# codec.net
KiCad netlist of a schematic drawn in Altium Designer
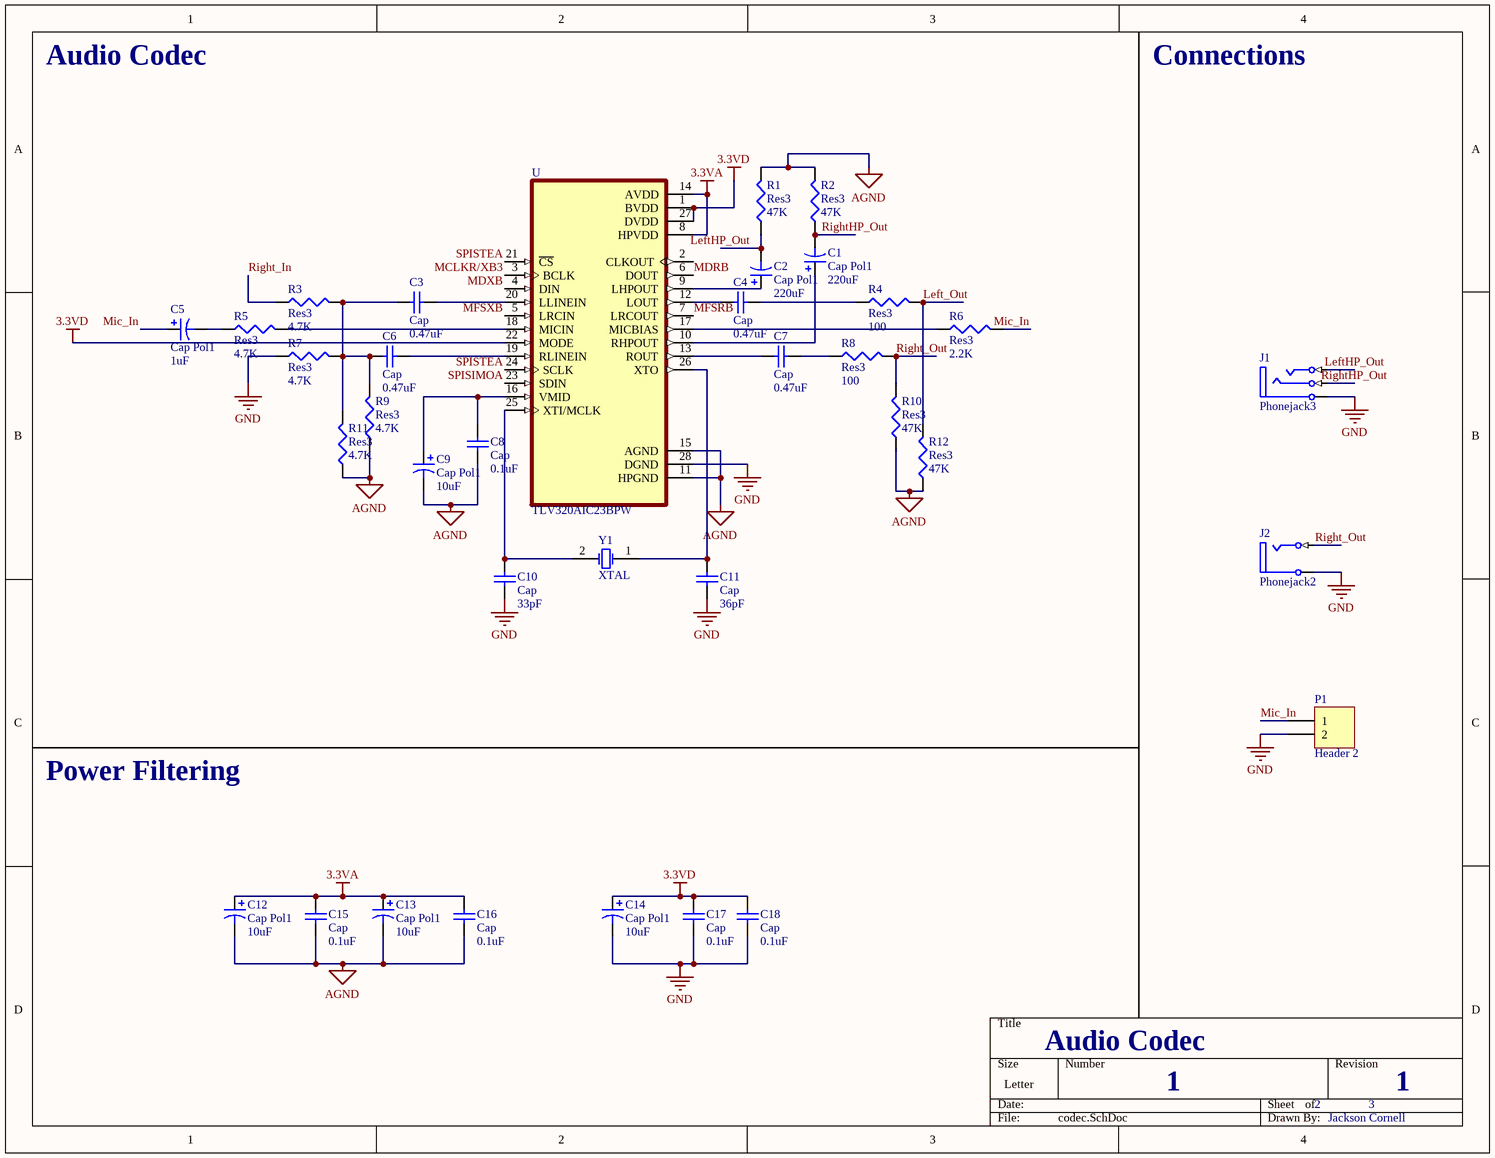
[diagram p0: codec.SchDoc]

(export (version "E")
  (design (tool "Eeschema 10.0.6"))
  (components
    (comp (ref "C1")
      (value "Cap Pol1")
      (footprint "RB7.6-15")
      (description "Polarized Capacitor (Radial)")
      (fields (field (name "ALTIUM_VALUE") "220uF") (field (name "PUBLISHER") "Altium Limited"))
      (libsource (lib "Miscellaneous Devices") (part "Cap Pol1"))
    )
    (comp (ref "C2")
      (value "Cap Pol1")
      (footprint "RB7.6-15")
      (description "Polarized Capacitor (Radial)")
      (fields (field (name "ALTIUM_VALUE") "220uF") (field (name "PUBLISHER") "Altium Limited"))
      (libsource (lib "Miscellaneous Devices") (part "Cap Pol1"))
    )
    (comp (ref "C3")
      (value "Cap")
      (footprint "RAD-0.3")
      (description "Capacitor")
      (fields (field (name "ALTIUM_VALUE") "0.47uF") (field (name "PUBLISHER") "Altium Limited"))
      (libsource (lib "Miscellaneous Devices") (part "Cap"))
    )
    (comp (ref "C4")
      (value "Cap")
      (footprint "RAD-0.3")
      (description "Capacitor")
      (fields (field (name "ALTIUM_VALUE") "0.47uF") (field (name "PUBLISHER") "Altium Limited"))
      (libsource (lib "Miscellaneous Devices") (part "Cap"))
    )
    (comp (ref "C5")
      (value "Cap Pol1")
      (footprint "RB7.6-15")
      (description "Polarized Capacitor (Radial)")
      (fields (field (name "ALTIUM_VALUE") "1uF") (field (name "PUBLISHER") "Altium Limited"))
      (libsource (lib "Miscellaneous Devices") (part "Cap Pol1"))
    )
    (comp (ref "C6")
      (value "Cap")
      (footprint "RAD-0.3")
      (description "Capacitor")
      (fields (field (name "ALTIUM_VALUE") "0.47uF") (field (name "PUBLISHER") "Altium Limited"))
      (libsource (lib "Miscellaneous Devices") (part "Cap"))
    )
    (comp (ref "C7")
      (value "Cap")
      (footprint "RAD-0.3")
      (description "Capacitor")
      (fields (field (name "ALTIUM_VALUE") "0.47uF") (field (name "PUBLISHER") "Altium Limited"))
      (libsource (lib "Miscellaneous Devices") (part "Cap"))
    )
    (comp (ref "C8")
      (value "Cap")
      (footprint "RAD-0.3")
      (description "Capacitor")
      (fields (field (name "ALTIUM_VALUE") "0.1uF") (field (name "PUBLISHER") "Altium Limited"))
      (libsource (lib "Miscellaneous Devices") (part "Cap"))
    )
    (comp (ref "C9")
      (value "Cap Pol1")
      (footprint "RB7.6-15")
      (description "Polarized Capacitor (Radial)")
      (fields (field (name "ALTIUM_VALUE") "10uF") (field (name "PUBLISHER") "Altium Limited"))
      (libsource (lib "Miscellaneous Devices") (part "Cap Pol1"))
    )
    (comp (ref "C10")
      (value "Cap")
      (footprint "RAD-0.3")
      (description "Capacitor")
      (fields (field (name "ALTIUM_VALUE") "33pF") (field (name "PUBLISHER") "Altium Limited"))
      (libsource (lib "Miscellaneous Devices") (part "Cap"))
    )
    (comp (ref "C11")
      (value "Cap")
      (footprint "RAD-0.3")
      (description "Capacitor")
      (fields (field (name "ALTIUM_VALUE") "36pF") (field (name "PUBLISHER") "Altium Limited"))
      (libsource (lib "Miscellaneous Devices") (part "Cap"))
    )
    (comp (ref "C12")
      (value "Cap Pol1")
      (footprint "RB7.6-15")
      (description "Polarized Capacitor (Radial)")
      (fields (field (name "ALTIUM_VALUE") "10uF") (field (name "PUBLISHER") "Altium Limited"))
      (libsource (lib "Miscellaneous Devices") (part "Cap Pol1"))
    )
    (comp (ref "C13")
      (value "Cap Pol1")
      (footprint "RB7.6-15")
      (description "Polarized Capacitor (Radial)")
      (fields (field (name "ALTIUM_VALUE") "10uF") (field (name "PUBLISHER") "Altium Limited"))
      (libsource (lib "Miscellaneous Devices") (part "Cap Pol1"))
    )
    (comp (ref "C14")
      (value "Cap Pol1")
      (footprint "RB7.6-15")
      (description "Polarized Capacitor (Radial)")
      (fields (field (name "ALTIUM_VALUE") "10uF") (field (name "PUBLISHER") "Altium Limited"))
      (libsource (lib "Miscellaneous Devices") (part "Cap Pol1"))
    )
    (comp (ref "C15")
      (value "Cap")
      (footprint "RAD-0.3")
      (description "Capacitor")
      (fields (field (name "ALTIUM_VALUE") "0.1uF") (field (name "PUBLISHER") "Altium Limited"))
      (libsource (lib "Miscellaneous Devices") (part "Cap"))
    )
    (comp (ref "C16")
      (value "Cap")
      (footprint "RAD-0.3")
      (description "Capacitor")
      (fields (field (name "ALTIUM_VALUE") "0.1uF") (field (name "PUBLISHER") "Altium Limited"))
      (libsource (lib "Miscellaneous Devices") (part "Cap"))
    )
    (comp (ref "C17")
      (value "Cap")
      (footprint "RAD-0.3")
      (description "Capacitor")
      (fields (field (name "ALTIUM_VALUE") "0.1uF") (field (name "PUBLISHER") "Altium Limited"))
      (libsource (lib "Miscellaneous Devices") (part "Cap"))
    )
    (comp (ref "C18")
      (value "Cap")
      (footprint "RAD-0.3")
      (description "Capacitor")
      (fields (field (name "ALTIUM_VALUE") "0.1uF") (field (name "PUBLISHER") "Altium Limited"))
      (libsource (lib "Miscellaneous Devices") (part "Cap"))
    )
    (comp (ref "J1")
      (value "Phonejack3")
      (footprint "JACK/6-V3")
      (description "Jack Socket, 1/4\" [6.5mm], Thru-Hole, Vertical, 3-Conductor Open Circuit (Non-Normalling)")
      (fields (field (name "PUBLISHER") "Altium Limited"))
      (libsource (lib "Miscellaneous Connectors") (part "Phonejack3"))
    )
    (comp (ref "J2")
      (value "Phonejack2")
      (footprint "JACK/6-V2")
      (description "Jack Socket, 1/4\" [6.5mm], Thru-Hole, Vertical, 2-Conductor Open Circuit")
      (fields (field (name "PUBLISHER") "Altium Limited"))
      (libsource (lib "Miscellaneous Connectors") (part "Phonejack2"))
    )
    (comp (ref "P1")
      (value "Header 2")
      (footprint "HDR1X2")
      (description "Header, 2-Pin")
      (fields (field (name "PUBLISHER") "Altium Limited"))
      (libsource (lib "Miscellaneous Connectors") (part "Header 2"))
    )
    (comp (ref "R1")
      (value "Res3")
      (footprint "J1-0603")
      (description "Resistor")
      (fields (field (name "ALTIUM_VALUE") "47K") (field (name "PUBLISHER") "Altium Limited"))
      (libsource (lib "Miscellaneous Devices") (part "Res3"))
    )
    (comp (ref "R2")
      (value "Res3")
      (footprint "J1-0603")
      (description "Resistor")
      (fields (field (name "ALTIUM_VALUE") "47K") (field (name "PUBLISHER") "Altium Limited"))
      (libsource (lib "Miscellaneous Devices") (part "Res3"))
    )
    (comp (ref "R3")
      (value "Res3")
      (footprint "J1-0603")
      (description "Resistor")
      (fields (field (name "ALTIUM_VALUE") "4.7K") (field (name "PUBLISHER") "Altium Limited"))
      (libsource (lib "Miscellaneous Devices") (part "Res3"))
    )
    (comp (ref "R4")
      (value "Res3")
      (footprint "J1-0603")
      (description "Resistor")
      (fields (field (name "ALTIUM_VALUE") "100") (field (name "PUBLISHER") "Altium Limited"))
      (libsource (lib "Miscellaneous Devices") (part "Res3"))
    )
    (comp (ref "R5")
      (value "Res3")
      (footprint "J1-0603")
      (description "Resistor")
      (fields (field (name "ALTIUM_VALUE") "4.7K") (field (name "PUBLISHER") "Altium Limited"))
      (libsource (lib "Miscellaneous Devices") (part "Res3"))
    )
    (comp (ref "R6")
      (value "Res3")
      (footprint "J1-0603")
      (description "Resistor")
      (fields (field (name "ALTIUM_VALUE") "2.2K") (field (name "PUBLISHER") "Altium Limited"))
      (libsource (lib "Miscellaneous Devices") (part "Res3"))
    )
    (comp (ref "R7")
      (value "Res3")
      (footprint "J1-0603")
      (description "Resistor")
      (fields (field (name "ALTIUM_VALUE") "4.7K") (field (name "PUBLISHER") "Altium Limited"))
      (libsource (lib "Miscellaneous Devices") (part "Res3"))
    )
    (comp (ref "R8")
      (value "Res3")
      (footprint "J1-0603")
      (description "Resistor")
      (fields (field (name "ALTIUM_VALUE") "100") (field (name "PUBLISHER") "Altium Limited"))
      (libsource (lib "Miscellaneous Devices") (part "Res3"))
    )
    (comp (ref "R9")
      (value "Res3")
      (footprint "J1-0603")
      (description "Resistor")
      (fields (field (name "ALTIUM_VALUE") "4.7K") (field (name "PUBLISHER") "Altium Limited"))
      (libsource (lib "Miscellaneous Devices") (part "Res3"))
    )
    (comp (ref "R10")
      (value "Res3")
      (footprint "J1-0603")
      (description "Resistor")
      (fields (field (name "ALTIUM_VALUE") "47K") (field (name "PUBLISHER") "Altium Limited"))
      (libsource (lib "Miscellaneous Devices") (part "Res3"))
    )
    (comp (ref "R11")
      (value "Res3")
      (footprint "J1-0603")
      (description "Resistor")
      (fields (field (name "ALTIUM_VALUE") "4.7K") (field (name "PUBLISHER") "Altium Limited"))
      (libsource (lib "Miscellaneous Devices") (part "Res3"))
    )
    (comp (ref "R12")
      (value "Res3")
      (footprint "J1-0603")
      (description "Resistor")
      (fields (field (name "ALTIUM_VALUE") "47K") (field (name "PUBLISHER") "Altium Limited"))
      (libsource (lib "Miscellaneous Devices") (part "Res3"))
    )
    (comp (ref "U")
      (value "TLV320AIC23BPW")
      (footprint "SOP65P640X120-28N")
      (description "Low-Power Stereo CODEC with HP Amplifier 28-TSSOP -10 to 70")
      (fields (field (name "MF") "Texas Instruments"))
      (libsource (lib "TLV320AIC23BPW") (part "TLV320AIC23BPW"))
    )
    (comp (ref "Y1")
      (value "XTAL")
      (footprint "R38")
      (description "Crystal Oscillator")
      (fields (field (name "PUBLISHER") "Altium Limited"))
      (libsource (lib "Miscellaneous Devices") (part "XTAL"))
    )
  )
  (nets
    (net (code "1") (name "/LeftHP_Out") (class "Default")
      (node (ref "C2") (pin "2") (pinfunction "2_2") (pintype "passive"))
      (node (ref "J1") (pin "1") (pinfunction "T_1") (pintype "input"))
      (node (ref "R1") (pin "1") (pinfunction "1_1") (pintype "passive"))
    )
    (net (code "2") (name "/Left_Out") (class "Default")
      (node (ref "R12") (pin "2") (pinfunction "2_2") (pintype "passive"))
      (node (ref "R4") (pin "2") (pinfunction "2_2") (pintype "passive"))
    )
    (net (code "3") (name "/MCLKR{slash}XB3") (class "Default")
      (node (ref "U") (pin "3") (pinfunction "BCLK_3") (pintype "input"))
    )
    (net (code "4") (name "/MDRB") (class "Default")
      (node (ref "U") (pin "6") (pinfunction "DOUT_6") (pintype "output"))
    )
    (net (code "5") (name "/MDXB") (class "Default")
      (node (ref "U") (pin "4") (pinfunction "DIN_4") (pintype "input"))
    )
    (net (code "6") (name "/MFSRB") (class "Default")
      (node (ref "U") (pin "7") (pinfunction "LRCOUT_7") (pintype "output"))
    )
    (net (code "7") (name "/MFSXB") (class "Default")
      (node (ref "U") (pin "5") (pinfunction "LRCIN_5") (pintype "input"))
    )
    (net (code "8") (name "/Mic_In") (class "Default")
      (node (ref "C5") (pin "1") (pinfunction "1_1") (pintype "passive"))
      (node (ref "P1") (pin "1") (pinfunction "1_1") (pintype "passive"))
      (node (ref "R6") (pin "2") (pinfunction "2_2") (pintype "passive"))
    )
    (net (code "9") (name "/RightHP_Out") (class "Default")
      (node (ref "C1") (pin "2") (pinfunction "2_2") (pintype "passive"))
      (node (ref "J1") (pin "3") (pinfunction "R_3") (pintype "input"))
      (node (ref "R2") (pin "1") (pinfunction "1_1") (pintype "passive"))
    )
    (net (code "10") (name "/Right_In") (class "Default")
      (node (ref "R3") (pin "1") (pinfunction "1_1") (pintype "passive"))
    )
    (net (code "11") (name "/Right_Out") (class "Default")
      (node (ref "J2") (pin "1") (pinfunction "T_1") (pintype "input"))
      (node (ref "R10") (pin "2") (pinfunction "2_2") (pintype "passive"))
      (node (ref "R8") (pin "2") (pinfunction "2_2") (pintype "passive"))
    )
    (net (code "12") (name "/SPISIMOA") (class "Default")
      (node (ref "U") (pin "23") (pinfunction "SDIN_23") (pintype "input"))
    )
    (net (code "13") (name "/SPISTEA") (class "Default")
      (node (ref "U") (pin "21") (pinfunction "~{CS}_21") (pintype "input"))
      (node (ref "U") (pin "24") (pinfunction "SCLK_24") (pintype "input"))
    )
    (net (code "14") (name "3.3VA") (class "Default")
      (node (ref "C12") (pin "1") (pinfunction "1_1") (pintype "passive"))
      (node (ref "C13") (pin "1") (pinfunction "1_1") (pintype "passive"))
      (node (ref "C15") (pin "1") (pinfunction "1_1") (pintype "passive"))
      (node (ref "C16") (pin "1") (pinfunction "1_1") (pintype "passive"))
      (node (ref "U") (pin "14") (pinfunction "AVDD_14") (pintype "power_in"))
      (node (ref "U") (pin "8") (pinfunction "HPVDD_8") (pintype "power_in"))
    )
    (net (code "15") (name "3.3VD") (class "Default")
      (node (ref "C14") (pin "1") (pinfunction "1_1") (pintype "passive"))
      (node (ref "C17") (pin "2") (pinfunction "2_2") (pintype "passive"))
      (node (ref "C18") (pin "2") (pinfunction "2_2") (pintype "passive"))
      (node (ref "U") (pin "1") (pinfunction "BVDD_1") (pintype "power_in"))
      (node (ref "U") (pin "22") (pinfunction "MODE_22") (pintype "input"))
      (node (ref "U") (pin "27") (pinfunction "DVDD_27") (pintype "power_in"))
    )
    (net (code "16") (name "AGND") (class "Default")
      (node (ref "C12") (pin "2") (pinfunction "2_2") (pintype "passive"))
      (node (ref "C13") (pin "2") (pinfunction "2_2") (pintype "passive"))
      (node (ref "C15") (pin "2") (pinfunction "2_2") (pintype "passive"))
      (node (ref "C16") (pin "2") (pinfunction "2_2") (pintype "passive"))
      (node (ref "C8") (pin "1") (pinfunction "1_1") (pintype "passive"))
      (node (ref "C9") (pin "2") (pinfunction "2_2") (pintype "passive"))
      (node (ref "R1") (pin "2") (pinfunction "2_2") (pintype "passive"))
      (node (ref "R10") (pin "1") (pinfunction "1_1") (pintype "passive"))
      (node (ref "R11") (pin "1") (pinfunction "1_1") (pintype "passive"))
      (node (ref "R12") (pin "1") (pinfunction "1_1") (pintype "passive"))
      (node (ref "R2") (pin "2") (pinfunction "2_2") (pintype "passive"))
      (node (ref "R9") (pin "1") (pinfunction "1_1") (pintype "passive"))
      (node (ref "U") (pin "11") (pinfunction "HPGND_11") (pintype "power_in"))
      (node (ref "U") (pin "15") (pinfunction "AGND_15") (pintype "power_in"))
    )
    (net (code "17") (name "GND") (class "Default")
      (node (ref "C10") (pin "2") (pinfunction "2_2") (pintype "passive"))
      (node (ref "C11") (pin "2") (pinfunction "2_2") (pintype "passive"))
      (node (ref "C14") (pin "2") (pinfunction "2_2") (pintype "passive"))
      (node (ref "C17") (pin "1") (pinfunction "1_1") (pintype "passive"))
      (node (ref "C18") (pin "1") (pinfunction "1_1") (pintype "passive"))
      (node (ref "J1") (pin "5") (pinfunction "S_5") (pintype "power_in"))
      (node (ref "J2") (pin "5") (pinfunction "S_5") (pintype "power_in"))
      (node (ref "P1") (pin "2") (pinfunction "2_2") (pintype "passive"))
      (node (ref "R7") (pin "1") (pinfunction "1_1") (pintype "passive"))
      (node (ref "U") (pin "28") (pinfunction "DGND_28") (pintype "power_in"))
    )
    (net (code "18") (name "Net-(C3-Pad1)") (class "Default")
      (node (ref "C3") (pin "1") (pinfunction "1_1") (pintype "passive"))
      (node (ref "C6") (pin "1") (pinfunction "1_1") (pintype "passive"))
      (node (ref "R11") (pin "2") (pinfunction "2_2") (pintype "passive"))
      (node (ref "R3") (pin "2") (pinfunction "2_2") (pintype "passive"))
      (node (ref "R7") (pin "2") (pinfunction "2_2") (pintype "passive"))
      (node (ref "R9") (pin "2") (pinfunction "2_2") (pintype "passive"))
    )
    (net (code "19") (name "Net-(C4-Pad2)") (class "Default")
      (node (ref "C4") (pin "2") (pinfunction "2_2") (pintype "passive"))
      (node (ref "R4") (pin "1") (pinfunction "1_1") (pintype "passive"))
    )
    (net (code "20") (name "Net-(C5-Pad2)") (class "Default")
      (node (ref "C5") (pin "2") (pinfunction "2_2") (pintype "passive"))
      (node (ref "R5") (pin "1") (pinfunction "1_1") (pintype "passive"))
    )
    (net (code "21") (name "Net-(C7-Pad2)") (class "Default")
      (node (ref "C7") (pin "2") (pinfunction "2_2") (pintype "passive"))
      (node (ref "R8") (pin "1") (pinfunction "1_1") (pintype "passive"))
    )
    (net (code "22") (name "Net-(U-LHPOUT)") (class "Default")
      (node (ref "C2") (pin "1") (pinfunction "1_1") (pintype "passive"))
      (node (ref "U") (pin "9") (pinfunction "LHPOUT_9") (pintype "output"))
    )
    (net (code "23") (name "Net-(U-LLINEIN)") (class "Default")
      (node (ref "C3") (pin "2") (pinfunction "2_2") (pintype "passive"))
      (node (ref "U") (pin "20") (pinfunction "LLINEIN_20") (pintype "input"))
    )
    (net (code "24") (name "Net-(U-LOUT)") (class "Default")
      (node (ref "C4") (pin "1") (pinfunction "1_1") (pintype "passive"))
      (node (ref "U") (pin "12") (pinfunction "LOUT_12") (pintype "output"))
    )
    (net (code "25") (name "Net-(U-MICBIAS)") (class "Default")
      (node (ref "R6") (pin "1") (pinfunction "1_1") (pintype "passive"))
      (node (ref "U") (pin "17") (pinfunction "MICBIAS_17") (pintype "output"))
    )
    (net (code "26") (name "Net-(U-MICIN)") (class "Default")
      (node (ref "R5") (pin "2") (pinfunction "2_2") (pintype "passive"))
      (node (ref "U") (pin "18") (pinfunction "MICIN_18") (pintype "input"))
    )
    (net (code "27") (name "Net-(U-RHPOUT)") (class "Default")
      (node (ref "C1") (pin "1") (pinfunction "1_1") (pintype "passive"))
      (node (ref "U") (pin "10") (pinfunction "RHPOUT_10") (pintype "output"))
    )
    (net (code "28") (name "Net-(U-RLINEIN)") (class "Default")
      (node (ref "C6") (pin "2") (pinfunction "2_2") (pintype "passive"))
      (node (ref "U") (pin "19") (pinfunction "RLINEIN_19") (pintype "input"))
    )
    (net (code "29") (name "Net-(U-ROUT)") (class "Default")
      (node (ref "C7") (pin "1") (pinfunction "1_1") (pintype "passive"))
      (node (ref "U") (pin "13") (pinfunction "ROUT_13") (pintype "output"))
    )
    (net (code "30") (name "Net-(U-VMID)") (class "Default")
      (node (ref "C8") (pin "2") (pinfunction "2_2") (pintype "passive"))
      (node (ref "C9") (pin "1") (pinfunction "1_1") (pintype "passive"))
      (node (ref "U") (pin "16") (pinfunction "VMID_16") (pintype "input"))
    )
    (net (code "31") (name "Net-(U-XTI{slash}MCLK)") (class "Default")
      (node (ref "C10") (pin "1") (pinfunction "1_1") (pintype "passive"))
      (node (ref "U") (pin "25") (pinfunction "XTI/MCLK_25") (pintype "input"))
      (node (ref "Y1") (pin "2") (pinfunction "OSC2_2") (pintype "passive"))
    )
    (net (code "32") (name "Net-(U-XTO)") (class "Default")
      (node (ref "C11") (pin "1") (pinfunction "1_1") (pintype "passive"))
      (node (ref "U") (pin "26") (pinfunction "XTO_26") (pintype "output"))
      (node (ref "Y1") (pin "1") (pinfunction "OSC1_1") (pintype "passive"))
    )
    (net (code "33") (name "unconnected-(U-CLKOUT-Pad2)") (class "Default")
      (node (ref "U") (pin "2") (pinfunction "CLKOUT_2") (pintype "output"))
    )
  )
)
